# ws_pcb.net
KiCad netlist of a schematic drawn in Altium Designer
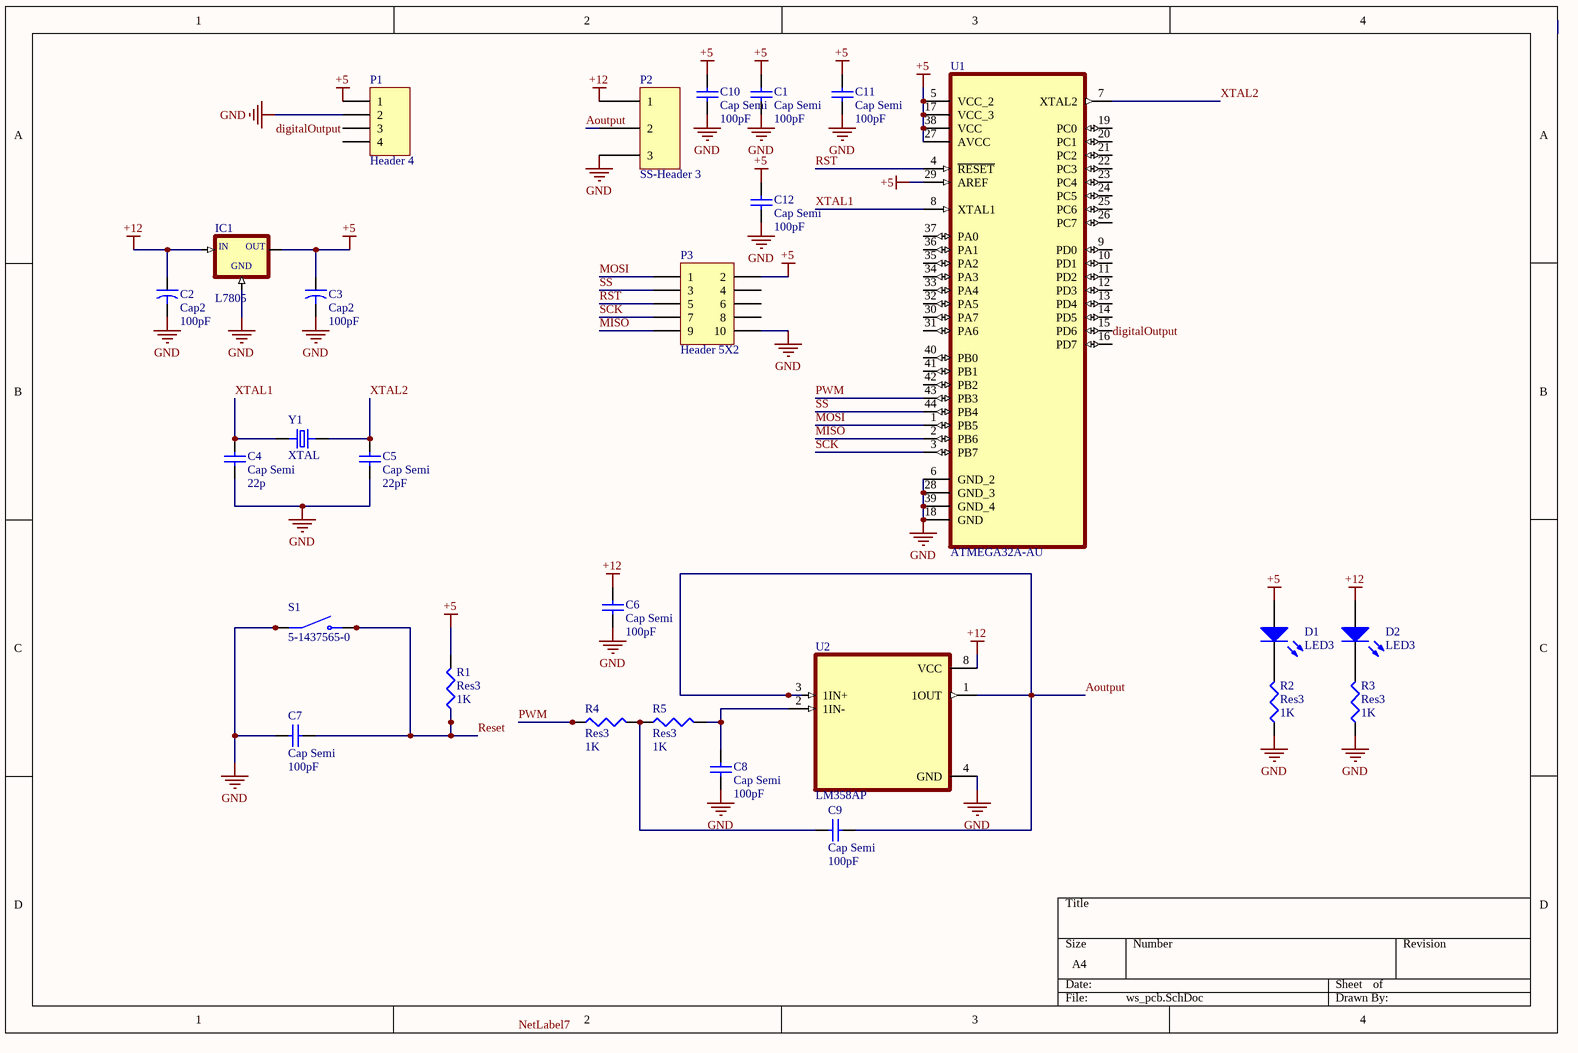
[diagram p0: ws_pcb.SchDoc]

(export (version "E")
  (design (tool "Eeschema 10.0.6"))
  (components
    (comp (ref "C1")
      (value "Cap Semi")
      (footprint "C1210")
      (description "Capacitor (Semiconductor SIM Model)")
      (fields (field (name "ALTIUM_VALUE") "100pF") (field (name "PUBLISHER") "Altium Limited"))
      (libsource (lib "Miscellaneous Devices") (part "Cap Semi"))
    )
    (comp (ref "C2")
      (value "Cap2")
      (footprint "CAPR5-4X5")
      (description "Capacitor")
      (fields (field (name "ALTIUM_VALUE") "100pF") (field (name "PUBLISHER") "Altium Limited"))
      (libsource (lib "Miscellaneous Devices") (part "Cap2"))
    )
    (comp (ref "C3")
      (value "Cap2")
      (footprint "CAPR5-4X5")
      (description "Capacitor")
      (fields (field (name "ALTIUM_VALUE") "100pF") (field (name "PUBLISHER") "Altium Limited"))
      (libsource (lib "Miscellaneous Devices") (part "Cap2"))
    )
    (comp (ref "C4")
      (value "Cap Semi")
      (footprint "C1210")
      (description "Capacitor (Semiconductor SIM Model)")
      (fields (field (name "ALTIUM_VALUE") "22p") (field (name "PUBLISHER") "Altium Limited"))
      (libsource (lib "Miscellaneous Devices") (part "Cap Semi"))
    )
    (comp (ref "C5")
      (value "Cap Semi")
      (footprint "C1210")
      (description "Capacitor (Semiconductor SIM Model)")
      (fields (field (name "ALTIUM_VALUE") "22pF") (field (name "PUBLISHER") "Altium Limited"))
      (libsource (lib "Miscellaneous Devices") (part "Cap Semi"))
    )
    (comp (ref "C6")
      (value "Cap Semi")
      (footprint "C1210")
      (description "Capacitor (Semiconductor SIM Model)")
      (fields (field (name "ALTIUM_VALUE") "100pF") (field (name "PUBLISHER") "Altium Limited"))
      (libsource (lib "Miscellaneous Devices") (part "Cap Semi"))
    )
    (comp (ref "C7")
      (value "Cap Semi")
      (footprint "C1210")
      (description "Capacitor (Semiconductor SIM Model)")
      (fields (field (name "ALTIUM_VALUE") "100pF") (field (name "PUBLISHER") "Altium Limited"))
      (libsource (lib "Miscellaneous Devices") (part "Cap Semi"))
    )
    (comp (ref "C8")
      (value "Cap Semi")
      (footprint "C1210")
      (description "Capacitor (Semiconductor SIM Model)")
      (fields (field (name "ALTIUM_VALUE") "100pF") (field (name "PUBLISHER") "Altium Limited"))
      (libsource (lib "Miscellaneous Devices") (part "Cap Semi"))
    )
    (comp (ref "C9")
      (value "Cap Semi")
      (footprint "C1210")
      (description "Capacitor (Semiconductor SIM Model)")
      (fields (field (name "ALTIUM_VALUE") "100pF") (field (name "PUBLISHER") "Altium Limited"))
      (libsource (lib "Miscellaneous Devices") (part "Cap Semi"))
    )
    (comp (ref "C10")
      (value "Cap Semi")
      (footprint "C1210")
      (description "Capacitor (Semiconductor SIM Model)")
      (fields (field (name "ALTIUM_VALUE") "100pF") (field (name "PUBLISHER") "Altium Limited"))
      (libsource (lib "Miscellaneous Devices") (part "Cap Semi"))
    )
    (comp (ref "C11")
      (value "Cap Semi")
      (footprint "C1210")
      (description "Capacitor (Semiconductor SIM Model)")
      (fields (field (name "ALTIUM_VALUE") "100pF") (field (name "PUBLISHER") "Altium Limited"))
      (libsource (lib "Miscellaneous Devices") (part "Cap Semi"))
    )
    (comp (ref "C12")
      (value "Cap Semi")
      (footprint "C1210")
      (description "Capacitor (Semiconductor SIM Model)")
      (fields (field (name "ALTIUM_VALUE") "100pF") (field (name "PUBLISHER") "Altium Limited"))
      (libsource (lib "Miscellaneous Devices") (part "Cap Semi"))
    )
    (comp (ref "D1")
      (value "LED3")
      (footprint "3.5X2.8X1.9")
      (description "Typical BLUE SiC LED")
      (fields (field (name "PUBLISHER") "Altium Limited"))
      (libsource (lib "Miscellaneous Devices") (part "LED3"))
    )
    (comp (ref "D2")
      (value "LED3")
      (footprint "3.5X2.8X1.9")
      (description "Typical BLUE SiC LED")
      (fields (field (name "PUBLISHER") "Altium Limited"))
      (libsource (lib "Miscellaneous Devices") (part "LED3"))
    )
    (comp (ref "IC1")
      (value "L7805")
      (footprint "78XXS")
      (description "Linear Voltage Regulator IC 1 Output 1.5A D2PAK")
      (fields (field (name "MF") "STMicroelectronics"))
      (libsource (lib "L7805") (part "L7805"))
    )
    (comp (ref "P1")
      (value "Header 4")
      (footprint "HDR1X4")
      (description "Header, 4-Pin")
      (fields (field (name "PUBLISHER") "Altium Limited"))
      (libsource (lib "Miscellaneous Connectors") (part "Header 4"))
    )
    (comp (ref "P2")
      (value "SS-Header 3")
      (footprint "PCBComponent_1")
      (description "Slimseal 3-Pin Connector")
      (libsource (lib "SS3PIN (1)") (part "Component_1"))
    )
    (comp (ref "P3")
      (value "Header 5X2")
      (footprint "HDR2X5")
      (description "Header, 5-Pin, Dual row")
      (fields (field (name "PUBLISHER") "Altium Limited"))
      (libsource (lib "Miscellaneous Connectors") (part "Header 5X2"))
    )
    (comp (ref "R1")
      (value "Res3")
      (footprint "14-1210")
      (description "Resistor")
      (fields (field (name "ALTIUM_VALUE") "1K") (field (name "PUBLISHER") "Altium Limited"))
      (libsource (lib "Miscellaneous Devices") (part "Res3"))
    )
    (comp (ref "R2")
      (value "Res3")
      (footprint "14-1210")
      (description "Resistor")
      (fields (field (name "ALTIUM_VALUE") "1K") (field (name "PUBLISHER") "Altium Limited"))
      (libsource (lib "Miscellaneous Devices") (part "Res3"))
    )
    (comp (ref "R3")
      (value "Res3")
      (footprint "14-1210")
      (description "Resistor")
      (fields (field (name "ALTIUM_VALUE") "1K") (field (name "PUBLISHER") "Altium Limited"))
      (libsource (lib "Miscellaneous Devices") (part "Res3"))
    )
    (comp (ref "R4")
      (value "Res3")
      (footprint "14-1210")
      (description "Resistor")
      (fields (field (name "ALTIUM_VALUE") "1K") (field (name "PUBLISHER") "Altium Limited"))
      (libsource (lib "Miscellaneous Devices") (part "Res3"))
    )
    (comp (ref "R5")
      (value "Res3")
      (footprint "14-1210")
      (description "Resistor")
      (fields (field (name "ALTIUM_VALUE") "1K") (field (name "PUBLISHER") "Altium Limited"))
      (libsource (lib "Miscellaneous Devices") (part "Res3"))
    )
    (comp (ref "S1")
      (value "5-1437565-0")
      (footprint "SW_5-1437565-0")
      (description "Tactile Switch SPST-NO Top Actuated Surface Mount")
      (fields (field (name "MF") "TE Connectivity"))
      (libsource (lib "5-1437565-0") (part "5-1437565-0"))
    )
    (comp (ref "U1")
      (value "ATMEGA32A-AU")
      (footprint "QFP80P1200X1200X120-44N")
      (description "AVR AVRÂ® ATmega Microcontroller IC 8-Bit 16MHz 32KB _16K x 16_ FLASH 44-TQFP _10x10_")
      (fields (field (name "MF") "Microchip"))
      (libsource (lib "ATMEGA32A-AU") (part "ATMEGA32A-AU"))
    )
    (comp (ref "U2")
      (value "LM358AP")
      (footprint "DIP794W45P254L959H508Q8")
      (description "Dual improved offset, standard operational amplifier<br /> &nbsp; 8-PDIP 0 to 70")
      (fields
        (field (name "MF") "Texas Instruments")
        (field (name "BUYPART") "https://www.snapeda.com/parts/LM358AP/Texas%20Instruments/view-part/214423/?ref=eda")
      )
      (libsource (lib "LM358AP") (part "LM358AP"))
    )
    (comp (ref "Y1")
      (value "XTAL")
      (footprint "XTAL_ECS-200-20-1X")
      (description "Crystals / Oscillators / Resonators 24.00014MHz 18pF")
      (fields (field (name "MF") "ECS International") (field (name "MP") "ECS-240.0001-18-1X"))
      (libsource (lib "ECS-240.0001-18-1X") (part "ECS-240.0001-18-1X"))
    )
  )
  (nets
    (net (code "1") (name "+5") (class "Default")
      (node (ref "C1") (pin "2") (pinfunction "2_2") (pintype "passive"))
      (node (ref "C10") (pin "2") (pinfunction "2_2") (pintype "passive"))
      (node (ref "C11") (pin "2") (pinfunction "2_2") (pintype "passive"))
      (node (ref "C12") (pin "2") (pinfunction "2_2") (pintype "passive"))
      (node (ref "C3") (pin "1") (pinfunction "1_1") (pintype "passive"))
      (node (ref "D1") (pin "1") (pinfunction "A_1") (pintype "passive"))
      (node (ref "IC1") (pin "OUT") (pinfunction "OUT_OUT") (pintype "passive"))
      (node (ref "P1") (pin "1") (pinfunction "1_1") (pintype "passive"))
      (node (ref "P3") (pin "2") (pinfunction "2_2") (pintype "passive"))
      (node (ref "R1") (pin "2") (pinfunction "2_2") (pintype "passive"))
      (node (ref "U1") (pin "17") (pinfunction "VCC_3_17") (pintype "power_in"))
      (node (ref "U1") (pin "27") (pinfunction "AVCC_27") (pintype "power_in"))
      (node (ref "U1") (pin "29") (pinfunction "AREF_29") (pintype "input"))
      (node (ref "U1") (pin "38") (pinfunction "VCC_38") (pintype "power_in"))
      (node (ref "U1") (pin "5") (pinfunction "VCC_2_5") (pintype "power_in"))
    )
    (net (code "2") (name "+12") (class "Default")
      (node (ref "C2") (pin "1") (pinfunction "1_1") (pintype "passive"))
      (node (ref "C6") (pin "2") (pinfunction "2_2") (pintype "passive"))
      (node (ref "D2") (pin "1") (pinfunction "A_1") (pintype "passive"))
      (node (ref "IC1") (pin "IN") (pinfunction "IN_IN") (pintype "input"))
      (node (ref "P2") (pin "1") (pinfunction "1_1") (pintype "passive"))
      (node (ref "U2") (pin "8") (pinfunction "VCC_8") (pintype "power_in"))
    )
    (net (code "3") (name "/Aoutput") (class "Default")
      (node (ref "C9") (pin "2") (pinfunction "2_2") (pintype "passive"))
      (node (ref "P2") (pin "2") (pinfunction "2_2") (pintype "passive"))
      (node (ref "U2") (pin "1") (pinfunction "1OUT_1") (pintype "output"))
      (node (ref "U2") (pin "3") (pinfunction "1IN+_3") (pintype "input"))
    )
    (net (code "4") (name "/MISO") (class "Default")
      (node (ref "P3") (pin "9") (pinfunction "9_9") (pintype "passive"))
      (node (ref "U1") (pin "2") (pinfunction "PB6_2") (pintype "bidirectional"))
    )
    (net (code "5") (name "/MOSI") (class "Default")
      (node (ref "P3") (pin "1") (pinfunction "1_1") (pintype "passive"))
      (node (ref "U1") (pin "1") (pinfunction "PB5_1") (pintype "bidirectional"))
    )
    (net (code "7") (name "/PWM") (class "Default")
      (node (ref "R4") (pin "1") (pinfunction "1_1") (pintype "passive"))
      (node (ref "U1") (pin "43") (pinfunction "PB3_43") (pintype "bidirectional"))
    )
    (net (code "8") (name "/RST") (class "Default")
      (node (ref "P3") (pin "5") (pinfunction "5_5") (pintype "passive"))
      (node (ref "U1") (pin "4") (pinfunction "~{RESET}_4") (pintype "input"))
    )
    (net (code "9") (name "/Reset") (class "Default")
      (node (ref "C7") (pin "1") (pinfunction "1_1") (pintype "passive"))
      (node (ref "R1") (pin "1") (pinfunction "1_1") (pintype "passive"))
      (node (ref "S1") (pin "3") (pinfunction "NO_3") (pintype "passive"))
      (node (ref "S1") (pin "4") (pinfunction "NO_4") (pintype "passive"))
    )
    (net (code "10") (name "/SCK") (class "Default")
      (node (ref "P3") (pin "7") (pinfunction "7_7") (pintype "passive"))
      (node (ref "U1") (pin "3") (pinfunction "PB7_3") (pintype "bidirectional"))
    )
    (net (code "11") (name "/SS") (class "Default")
      (node (ref "P3") (pin "3") (pinfunction "3_3") (pintype "passive"))
      (node (ref "U1") (pin "44") (pinfunction "PB4_44") (pintype "bidirectional"))
    )
    (net (code "12") (name "/XTAL1") (class "Default")
      (node (ref "C4") (pin "2") (pinfunction "2_2") (pintype "passive"))
      (node (ref "U1") (pin "8") (pinfunction "XTAL1_8") (pintype "input"))
      (node (ref "Y1") (pin "1") (pinfunction "1_1") (pintype "passive"))
    )
    (net (code "13") (name "/XTAL2") (class "Default")
      (node (ref "C5") (pin "2") (pinfunction "2_2") (pintype "passive"))
      (node (ref "U1") (pin "7") (pinfunction "XTAL2_7") (pintype "output"))
      (node (ref "Y1") (pin "2") (pinfunction "2_2") (pintype "passive"))
    )
    (net (code "14") (name "/digitalOutput") (class "Default")
      (node (ref "P1") (pin "3") (pinfunction "3_3") (pintype "passive"))
      (node (ref "U1") (pin "15") (pinfunction "PD6_15") (pintype "bidirectional"))
    )
    (net (code "15") (name "GND") (class "Default")
      (node (ref "C1") (pin "1") (pinfunction "1_1") (pintype "passive"))
      (node (ref "C10") (pin "1") (pinfunction "1_1") (pintype "passive"))
      (node (ref "C11") (pin "1") (pinfunction "1_1") (pintype "passive"))
      (node (ref "C12") (pin "1") (pinfunction "1_1") (pintype "passive"))
      (node (ref "C2") (pin "2") (pinfunction "2_2") (pintype "passive"))
      (node (ref "C3") (pin "2") (pinfunction "2_2") (pintype "passive"))
      (node (ref "C4") (pin "1") (pinfunction "1_1") (pintype "passive"))
      (node (ref "C5") (pin "1") (pinfunction "1_1") (pintype "passive"))
      (node (ref "C6") (pin "1") (pinfunction "1_1") (pintype "passive"))
      (node (ref "C7") (pin "2") (pinfunction "2_2") (pintype "passive"))
      (node (ref "C8") (pin "1") (pinfunction "1_1") (pintype "passive"))
      (node (ref "IC1") (pin "GND") (pinfunction "GND_GND") (pintype "input"))
      (node (ref "P1") (pin "2") (pinfunction "2_2") (pintype "passive"))
      (node (ref "P2") (pin "3") (pinfunction "3_3") (pintype "passive"))
      (node (ref "P3") (pin "10") (pinfunction "10_10") (pintype "passive"))
      (node (ref "R2") (pin "1") (pinfunction "1_1") (pintype "passive"))
      (node (ref "R3") (pin "1") (pinfunction "1_1") (pintype "passive"))
      (node (ref "S1") (pin "1") (pinfunction "COM_1") (pintype "passive"))
      (node (ref "S1") (pin "2") (pinfunction "COM_2") (pintype "passive"))
      (node (ref "U1") (pin "18") (pinfunction "GND_18") (pintype "passive"))
      (node (ref "U1") (pin "28") (pinfunction "GND_3_28") (pintype "passive"))
      (node (ref "U1") (pin "39") (pinfunction "GND_4_39") (pintype "passive"))
      (node (ref "U1") (pin "6") (pinfunction "GND_2_6") (pintype "passive"))
      (node (ref "U2") (pin "4") (pinfunction "GND_4") (pintype "power_in"))
    )
    (net (code "16") (name "Net-(C9-Pad1)") (class "Default")
      (node (ref "C9") (pin "1") (pinfunction "1_1") (pintype "passive"))
      (node (ref "R4") (pin "2") (pinfunction "2_2") (pintype "passive"))
      (node (ref "R5") (pin "1") (pinfunction "1_1") (pintype "passive"))
    )
    (net (code "17") (name "Net-(D1-K)") (class "Default")
      (node (ref "D1") (pin "2") (pinfunction "K_2") (pintype "passive"))
      (node (ref "R2") (pin "2") (pinfunction "2_2") (pintype "passive"))
    )
    (net (code "18") (name "Net-(D2-K)") (class "Default")
      (node (ref "D2") (pin "2") (pinfunction "K_2") (pintype "passive"))
      (node (ref "R3") (pin "2") (pinfunction "2_2") (pintype "passive"))
    )
    (net (code "19") (name "Net-(U2-1IN-)") (class "Default")
      (node (ref "C8") (pin "2") (pinfunction "2_2") (pintype "passive"))
      (node (ref "R5") (pin "2") (pinfunction "2_2") (pintype "passive"))
      (node (ref "U2") (pin "2") (pinfunction "1IN-_2") (pintype "input"))
    )
    (net (code "20") (name "unconnected-(P1-Pad4)") (class "Default")
      (node (ref "P1") (pin "4") (pinfunction "4_4") (pintype "passive"))
    )
    (net (code "21") (name "unconnected-(P3-Pad4)") (class "Default")
      (node (ref "P3") (pin "4") (pinfunction "4_4") (pintype "passive"))
    )
    (net (code "22") (name "unconnected-(P3-Pad6)") (class "Default")
      (node (ref "P3") (pin "6") (pinfunction "6_6") (pintype "passive"))
    )
    (net (code "23") (name "unconnected-(P3-Pad8)") (class "Default")
      (node (ref "P3") (pin "8") (pinfunction "8_8") (pintype "passive"))
    )
    (net (code "24") (name "unconnected-(U1-PA0-Pad37)") (class "Default")
      (node (ref "U1") (pin "37") (pinfunction "PA0_37") (pintype "bidirectional"))
    )
    (net (code "25") (name "unconnected-(U1-PA1-Pad36)") (class "Default")
      (node (ref "U1") (pin "36") (pinfunction "PA1_36") (pintype "bidirectional"))
    )
    (net (code "26") (name "unconnected-(U1-PA2-Pad35)") (class "Default")
      (node (ref "U1") (pin "35") (pinfunction "PA2_35") (pintype "bidirectional"))
    )
    (net (code "27") (name "unconnected-(U1-PA3-Pad34)") (class "Default")
      (node (ref "U1") (pin "34") (pinfunction "PA3_34") (pintype "bidirectional"))
    )
    (net (code "28") (name "unconnected-(U1-PA4-Pad33)") (class "Default")
      (node (ref "U1") (pin "33") (pinfunction "PA4_33") (pintype "bidirectional"))
    )
    (net (code "29") (name "unconnected-(U1-PA5-Pad32)") (class "Default")
      (node (ref "U1") (pin "32") (pinfunction "PA5_32") (pintype "bidirectional"))
    )
    (net (code "30") (name "unconnected-(U1-PA6-Pad31)") (class "Default")
      (node (ref "U1") (pin "31") (pinfunction "PA6_31") (pintype "bidirectional"))
    )
    (net (code "31") (name "unconnected-(U1-PA7-Pad30)") (class "Default")
      (node (ref "U1") (pin "30") (pinfunction "PA7_30") (pintype "bidirectional"))
    )
    (net (code "32") (name "unconnected-(U1-PB0-Pad40)") (class "Default")
      (node (ref "U1") (pin "40") (pinfunction "PB0_40") (pintype "bidirectional"))
    )
    (net (code "33") (name "unconnected-(U1-PB1-Pad41)") (class "Default")
      (node (ref "U1") (pin "41") (pinfunction "PB1_41") (pintype "bidirectional"))
    )
    (net (code "34") (name "unconnected-(U1-PB2-Pad42)") (class "Default")
      (node (ref "U1") (pin "42") (pinfunction "PB2_42") (pintype "bidirectional"))
    )
    (net (code "35") (name "unconnected-(U1-PC0-Pad19)") (class "Default")
      (node (ref "U1") (pin "19") (pinfunction "PC0_19") (pintype "bidirectional"))
    )
    (net (code "36") (name "unconnected-(U1-PC1-Pad20)") (class "Default")
      (node (ref "U1") (pin "20") (pinfunction "PC1_20") (pintype "bidirectional"))
    )
    (net (code "37") (name "unconnected-(U1-PC2-Pad21)") (class "Default")
      (node (ref "U1") (pin "21") (pinfunction "PC2_21") (pintype "bidirectional"))
    )
    (net (code "38") (name "unconnected-(U1-PC3-Pad22)") (class "Default")
      (node (ref "U1") (pin "22") (pinfunction "PC3_22") (pintype "bidirectional"))
    )
    (net (code "39") (name "unconnected-(U1-PC4-Pad23)") (class "Default")
      (node (ref "U1") (pin "23") (pinfunction "PC4_23") (pintype "bidirectional"))
    )
    (net (code "40") (name "unconnected-(U1-PC5-Pad24)") (class "Default")
      (node (ref "U1") (pin "24") (pinfunction "PC5_24") (pintype "bidirectional"))
    )
    (net (code "41") (name "unconnected-(U1-PC6-Pad25)") (class "Default")
      (node (ref "U1") (pin "25") (pinfunction "PC6_25") (pintype "bidirectional"))
    )
    (net (code "42") (name "unconnected-(U1-PC7-Pad26)") (class "Default")
      (node (ref "U1") (pin "26") (pinfunction "PC7_26") (pintype "bidirectional"))
    )
    (net (code "43") (name "unconnected-(U1-PD0-Pad9)") (class "Default")
      (node (ref "U1") (pin "9") (pinfunction "PD0_9") (pintype "bidirectional"))
    )
    (net (code "44") (name "unconnected-(U1-PD1-Pad10)") (class "Default")
      (node (ref "U1") (pin "10") (pinfunction "PD1_10") (pintype "bidirectional"))
    )
    (net (code "45") (name "unconnected-(U1-PD2-Pad11)") (class "Default")
      (node (ref "U1") (pin "11") (pinfunction "PD2_11") (pintype "bidirectional"))
    )
    (net (code "46") (name "unconnected-(U1-PD3-Pad12)") (class "Default")
      (node (ref "U1") (pin "12") (pinfunction "PD3_12") (pintype "bidirectional"))
    )
    (net (code "47") (name "unconnected-(U1-PD4-Pad13)") (class "Default")
      (node (ref "U1") (pin "13") (pinfunction "PD4_13") (pintype "bidirectional"))
    )
    (net (code "48") (name "unconnected-(U1-PD5-Pad14)") (class "Default")
      (node (ref "U1") (pin "14") (pinfunction "PD5_14") (pintype "bidirectional"))
    )
    (net (code "49") (name "unconnected-(U1-PD7-Pad16)") (class "Default")
      (node (ref "U1") (pin "16") (pinfunction "PD7_16") (pintype "bidirectional"))
    )
    (net (code "50") (name "unconnected-(U2-2IN+-Pad5)") (class "Default")
      (node (ref "U2") (pin "5") (pinfunction "2IN+_5") (pintype "input"))
    )
    (net (code "51") (name "unconnected-(U2-2IN--Pad6)") (class "Default")
      (node (ref "U2") (pin "6") (pinfunction "2IN-_6") (pintype "input"))
    )
    (net (code "52") (name "unconnected-(U2-2OUT-Pad7)") (class "Default")
      (node (ref "U2") (pin "7") (pinfunction "2OUT_7") (pintype "output"))
    )
  )
)
